# Breakout_V399.net
KiCad netlist of a schematic drawn in EAGLE
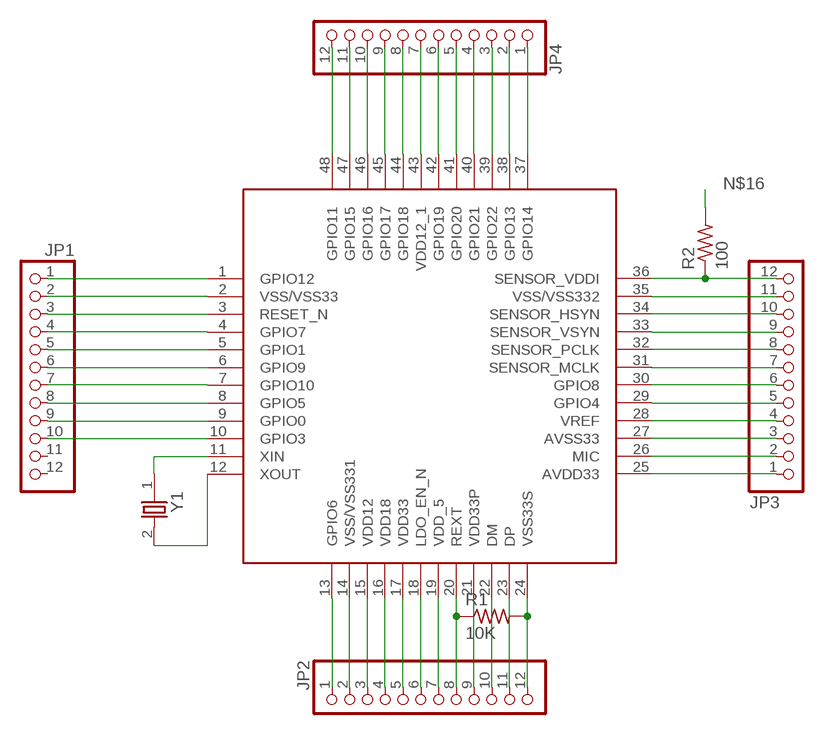
[diagram p0: schematic, sheet 1]

(export (version "E")
  (design (tool "Eeschema 10.0.6"))
  (components
    (comp (ref "JP1")
      (value "PINHD-1X12-CB")
      (footprint "eagle-import:1X12-CB")
      (libsource (lib "eagle-import") (part "PINHD-1X12-CB"))
    )
    (comp (ref "JP2")
      (value "PINHD-1X12-CB")
      (footprint "eagle-import:1X12-CB")
      (libsource (lib "eagle-import") (part "PINHD-1X12-CB"))
    )
    (comp (ref "JP3")
      (value "PINHD-1X12-CB")
      (footprint "eagle-import:1X12-CB")
      (libsource (lib "eagle-import") (part "PINHD-1X12-CB"))
    )
    (comp (ref "JP4")
      (value "PINHD-1X12-CB")
      (footprint "eagle-import:1X12-CB")
      (libsource (lib "eagle-import") (part "PINHD-1X12-CB"))
    )
    (comp (ref "R1")
      (value "10K")
      (footprint "eagle-import:R0402")
      (libsource (lib "eagle-import") (part "R-US_R0402"))
    )
    (comp (ref "R2")
      (value "100")
      (footprint "eagle-import:R0402")
      (libsource (lib "eagle-import") (part "R-US_R0402"))
    )
    (comp (ref "U1")
      (value "V399")
      (footprint "eagle-import:LQFP48")
      (libsource (lib "eagle-import") (part "V399"))
    )
    (comp (ref "Y1")
      (value "ABM3-29.4912MHZ-B2-T")
      (footprint "eagle-import:XTAL500X320X130N")
      (fields (field (name "MF") "Abracon"))
      (libsource (lib "eagle-import") (part "ABM3-29.4912MHZ-B2-T"))
    )
  )
  (nets
    (net (code "1") (name "/N$16") (class "Default")
      (node (ref "JP2") (pin "5") (pinfunction "5_5") (pintype "passive"))
      (node (ref "R2") (pin "2") (pinfunction "2_2") (pintype "passive"))
      (node (ref "U1") (pin "17") (pinfunction "VDD33_17") (pintype "bidirectional"))
    )
    (net (code "2") (name "Net-(U1-AVDD33)") (class "Default")
      (node (ref "JP3") (pin "1") (pinfunction "1_1") (pintype "passive"))
      (node (ref "U1") (pin "25") (pinfunction "AVDD33_25") (pintype "bidirectional"))
    )
    (net (code "3") (name "Net-(U1-AVSS33)") (class "Default")
      (node (ref "JP3") (pin "3") (pinfunction "3_3") (pintype "passive"))
      (node (ref "U1") (pin "27") (pinfunction "AVSS33_27") (pintype "bidirectional"))
    )
    (net (code "4") (name "Net-(U1-DM)") (class "Default")
      (node (ref "JP2") (pin "10") (pinfunction "10_10") (pintype "passive"))
      (node (ref "U1") (pin "22") (pinfunction "DM_22") (pintype "bidirectional"))
    )
    (net (code "5") (name "Net-(U1-DP)") (class "Default")
      (node (ref "JP2") (pin "11") (pinfunction "11_11") (pintype "passive"))
      (node (ref "U1") (pin "23") (pinfunction "DP_23") (pintype "bidirectional"))
    )
    (net (code "6") (name "Net-(U1-GPIO0)") (class "Default")
      (node (ref "JP1") (pin "9") (pinfunction "9_9") (pintype "passive"))
      (node (ref "U1") (pin "9") (pinfunction "GPIO0_9") (pintype "bidirectional"))
    )
    (net (code "7") (name "Net-(U1-GPIO1)") (class "Default")
      (node (ref "JP1") (pin "5") (pinfunction "5_5") (pintype "passive"))
      (node (ref "U1") (pin "5") (pinfunction "GPIO1_5") (pintype "bidirectional"))
    )
    (net (code "8") (name "Net-(U1-GPIO3)") (class "Default")
      (node (ref "JP1") (pin "10") (pinfunction "10_10") (pintype "passive"))
      (node (ref "U1") (pin "10") (pinfunction "GPIO3_10") (pintype "bidirectional"))
    )
    (net (code "9") (name "Net-(U1-GPIO4)") (class "Default")
      (node (ref "JP3") (pin "5") (pinfunction "5_5") (pintype "passive"))
      (node (ref "U1") (pin "29") (pinfunction "GPIO4_29") (pintype "bidirectional"))
    )
    (net (code "10") (name "Net-(U1-GPIO5)") (class "Default")
      (node (ref "JP1") (pin "8") (pinfunction "8_8") (pintype "passive"))
      (node (ref "U1") (pin "8") (pinfunction "GPIO5_8") (pintype "bidirectional"))
    )
    (net (code "11") (name "Net-(U1-GPIO6)") (class "Default")
      (node (ref "JP2") (pin "1") (pinfunction "1_1") (pintype "passive"))
      (node (ref "U1") (pin "13") (pinfunction "GPIO6_13") (pintype "bidirectional"))
    )
    (net (code "12") (name "Net-(U1-GPIO7)") (class "Default")
      (node (ref "JP1") (pin "4") (pinfunction "4_4") (pintype "passive"))
      (node (ref "U1") (pin "4") (pinfunction "GPIO7_4") (pintype "bidirectional"))
    )
    (net (code "13") (name "Net-(U1-GPIO8)") (class "Default")
      (node (ref "JP3") (pin "6") (pinfunction "6_6") (pintype "passive"))
      (node (ref "U1") (pin "30") (pinfunction "GPIO8_30") (pintype "bidirectional"))
    )
    (net (code "14") (name "Net-(U1-GPIO9)") (class "Default")
      (node (ref "JP1") (pin "6") (pinfunction "6_6") (pintype "passive"))
      (node (ref "U1") (pin "6") (pinfunction "GPIO9_6") (pintype "bidirectional"))
    )
    (net (code "15") (name "Net-(U1-GPIO10)") (class "Default")
      (node (ref "JP1") (pin "7") (pinfunction "7_7") (pintype "passive"))
      (node (ref "U1") (pin "7") (pinfunction "GPIO10_7") (pintype "bidirectional"))
    )
    (net (code "16") (name "Net-(U1-GPIO11)") (class "Default")
      (node (ref "JP4") (pin "12") (pinfunction "12_12") (pintype "passive"))
      (node (ref "U1") (pin "48") (pinfunction "GPIO11_48") (pintype "bidirectional"))
    )
    (net (code "17") (name "Net-(U1-GPIO12)") (class "Default")
      (node (ref "JP1") (pin "1") (pinfunction "1_1") (pintype "passive"))
      (node (ref "U1") (pin "1") (pinfunction "GPIO12_1") (pintype "bidirectional"))
    )
    (net (code "18") (name "Net-(U1-GPIO13)") (class "Default")
      (node (ref "JP4") (pin "2") (pinfunction "2_2") (pintype "passive"))
      (node (ref "U1") (pin "38") (pinfunction "GPIO13_38") (pintype "bidirectional"))
    )
    (net (code "19") (name "Net-(U1-GPIO14)") (class "Default")
      (node (ref "JP4") (pin "1") (pinfunction "1_1") (pintype "passive"))
      (node (ref "U1") (pin "37") (pinfunction "GPIO14_37") (pintype "bidirectional"))
    )
    (net (code "20") (name "Net-(U1-GPIO15)") (class "Default")
      (node (ref "JP4") (pin "11") (pinfunction "11_11") (pintype "passive"))
      (node (ref "U1") (pin "47") (pinfunction "GPIO15_47") (pintype "bidirectional"))
    )
    (net (code "21") (name "Net-(U1-GPIO16)") (class "Default")
      (node (ref "JP4") (pin "10") (pinfunction "10_10") (pintype "passive"))
      (node (ref "U1") (pin "46") (pinfunction "GPIO16_46") (pintype "bidirectional"))
    )
    (net (code "22") (name "Net-(U1-GPIO17)") (class "Default")
      (node (ref "JP4") (pin "9") (pinfunction "9_9") (pintype "passive"))
      (node (ref "U1") (pin "45") (pinfunction "GPIO17_45") (pintype "bidirectional"))
    )
    (net (code "23") (name "Net-(U1-GPIO18)") (class "Default")
      (node (ref "JP4") (pin "8") (pinfunction "8_8") (pintype "passive"))
      (node (ref "U1") (pin "44") (pinfunction "GPIO18_44") (pintype "bidirectional"))
    )
    (net (code "24") (name "Net-(U1-GPIO19)") (class "Default")
      (node (ref "JP4") (pin "6") (pinfunction "6_6") (pintype "passive"))
      (node (ref "U1") (pin "42") (pinfunction "GPIO19_42") (pintype "bidirectional"))
    )
    (net (code "25") (name "Net-(U1-GPIO20)") (class "Default")
      (node (ref "JP4") (pin "5") (pinfunction "5_5") (pintype "passive"))
      (node (ref "U1") (pin "41") (pinfunction "GPIO20_41") (pintype "bidirectional"))
    )
    (net (code "26") (name "Net-(U1-GPIO21)") (class "Default")
      (node (ref "JP4") (pin "4") (pinfunction "4_4") (pintype "passive"))
      (node (ref "U1") (pin "40") (pinfunction "GPIO21_40") (pintype "bidirectional"))
    )
    (net (code "27") (name "Net-(U1-GPIO22)") (class "Default")
      (node (ref "JP4") (pin "3") (pinfunction "3_3") (pintype "passive"))
      (node (ref "U1") (pin "39") (pinfunction "GPIO22_39") (pintype "bidirectional"))
    )
    (net (code "28") (name "Net-(U1-LDO_EN_N)") (class "Default")
      (node (ref "JP2") (pin "6") (pinfunction "6_6") (pintype "passive"))
      (node (ref "U1") (pin "18") (pinfunction "LDO_EN_N_18") (pintype "bidirectional"))
    )
    (net (code "29") (name "Net-(U1-MIC)") (class "Default")
      (node (ref "JP3") (pin "2") (pinfunction "2_2") (pintype "passive"))
      (node (ref "U1") (pin "26") (pinfunction "MIC_26") (pintype "bidirectional"))
    )
    (net (code "30") (name "Net-(U1-RESET_N)") (class "Default")
      (node (ref "JP1") (pin "3") (pinfunction "3_3") (pintype "passive"))
      (node (ref "U1") (pin "3") (pinfunction "RESET_N_3") (pintype "bidirectional"))
    )
    (net (code "31") (name "Net-(U1-REXT)") (class "Default")
      (node (ref "JP2") (pin "8") (pinfunction "8_8") (pintype "passive"))
      (node (ref "R1") (pin "1") (pinfunction "1_1") (pintype "passive"))
      (node (ref "U1") (pin "20") (pinfunction "REXT_20") (pintype "bidirectional"))
    )
    (net (code "32") (name "Net-(U1-SENSOR_HSYN)") (class "Default")
      (node (ref "JP3") (pin "10") (pinfunction "10_10") (pintype "passive"))
      (node (ref "U1") (pin "34") (pinfunction "SENSOR_HSYN_34") (pintype "bidirectional"))
    )
    (net (code "33") (name "Net-(U1-SENSOR_MCLK)") (class "Default")
      (node (ref "JP3") (pin "7") (pinfunction "7_7") (pintype "passive"))
      (node (ref "U1") (pin "31") (pinfunction "SENSOR_MCLK_31") (pintype "bidirectional"))
    )
    (net (code "34") (name "Net-(U1-SENSOR_PCLK)") (class "Default")
      (node (ref "JP3") (pin "8") (pinfunction "8_8") (pintype "passive"))
      (node (ref "U1") (pin "32") (pinfunction "SENSOR_PCLK_32") (pintype "bidirectional"))
    )
    (net (code "35") (name "Net-(U1-SENSOR_VDDI)") (class "Default")
      (node (ref "JP3") (pin "12") (pinfunction "12_12") (pintype "passive"))
      (node (ref "R2") (pin "1") (pinfunction "1_1") (pintype "passive"))
      (node (ref "U1") (pin "36") (pinfunction "SENSOR_VDDI_36") (pintype "bidirectional"))
    )
    (net (code "36") (name "Net-(U1-SENSOR_VSYN)") (class "Default")
      (node (ref "JP3") (pin "9") (pinfunction "9_9") (pintype "passive"))
      (node (ref "U1") (pin "33") (pinfunction "SENSOR_VSYN_33") (pintype "bidirectional"))
    )
    (net (code "37") (name "Net-(U1-VDD12)") (class "Default")
      (node (ref "JP2") (pin "3") (pinfunction "3_3") (pintype "passive"))
      (node (ref "U1") (pin "15") (pinfunction "VDD12_15") (pintype "bidirectional"))
    )
    (net (code "38") (name "Net-(U1-VDD12_1)") (class "Default")
      (node (ref "JP4") (pin "7") (pinfunction "7_7") (pintype "passive"))
      (node (ref "U1") (pin "43") (pinfunction "VDD12_1_43") (pintype "bidirectional"))
    )
    (net (code "39") (name "Net-(U1-VDD18)") (class "Default")
      (node (ref "JP2") (pin "4") (pinfunction "4_4") (pintype "passive"))
      (node (ref "U1") (pin "16") (pinfunction "VDD18_16") (pintype "bidirectional"))
    )
    (net (code "40") (name "Net-(U1-VDD33P)") (class "Default")
      (node (ref "JP2") (pin "9") (pinfunction "9_9") (pintype "passive"))
      (node (ref "U1") (pin "21") (pinfunction "VDD33P_21") (pintype "bidirectional"))
    )
    (net (code "41") (name "Net-(U1-VDD_5)") (class "Default")
      (node (ref "JP2") (pin "7") (pinfunction "7_7") (pintype "passive"))
      (node (ref "U1") (pin "19") (pinfunction "VDD_5_19") (pintype "bidirectional"))
    )
    (net (code "42") (name "Net-(U1-VREF)") (class "Default")
      (node (ref "JP3") (pin "4") (pinfunction "4_4") (pintype "passive"))
      (node (ref "U1") (pin "28") (pinfunction "VREF_28") (pintype "bidirectional"))
    )
    (net (code "43") (name "Net-(U1-VSS33S)") (class "Default")
      (node (ref "JP2") (pin "12") (pinfunction "12_12") (pintype "passive"))
      (node (ref "R1") (pin "2") (pinfunction "2_2") (pintype "passive"))
      (node (ref "U1") (pin "24") (pinfunction "VSS33S_24") (pintype "bidirectional"))
    )
    (net (code "44") (name "Net-(U1-VSS{slash}VSS33)") (class "Default")
      (node (ref "JP1") (pin "2") (pinfunction "2_2") (pintype "passive"))
      (node (ref "U1") (pin "2") (pinfunction "VSS/VSS33_2") (pintype "bidirectional"))
    )
    (net (code "45") (name "Net-(U1-VSS{slash}VSS331)") (class "Default")
      (node (ref "JP2") (pin "2") (pinfunction "2_2") (pintype "passive"))
      (node (ref "U1") (pin "14") (pinfunction "VSS/VSS331_14") (pintype "bidirectional"))
    )
    (net (code "46") (name "Net-(U1-VSS{slash}VSS332)") (class "Default")
      (node (ref "JP3") (pin "11") (pinfunction "11_11") (pintype "passive"))
      (node (ref "U1") (pin "35") (pinfunction "VSS/VSS332_35") (pintype "bidirectional"))
    )
    (net (code "47") (name "Net-(U1-XIN)") (class "Default")
      (node (ref "U1") (pin "11") (pinfunction "XIN_11") (pintype "bidirectional"))
      (node (ref "Y1") (pin "1") (pinfunction "1_1") (pintype "passive"))
    )
    (net (code "48") (name "Net-(U1-XOUT)") (class "Default")
      (node (ref "U1") (pin "12") (pinfunction "XOUT_12") (pintype "bidirectional"))
      (node (ref "Y1") (pin "2") (pinfunction "2_2") (pintype "passive"))
    )
    (net (code "49") (name "unconnected-(JP1-Pad11)") (class "Default")
      (node (ref "JP1") (pin "11") (pinfunction "11_11") (pintype "passive"))
    )
    (net (code "50") (name "unconnected-(JP1-Pad12)") (class "Default")
      (node (ref "JP1") (pin "12") (pinfunction "12_12") (pintype "passive"))
    )
  )
)
